# Tractive_System_Active_Light_rev4.net
KiCad netlist of a schematic drawn in EAGLE
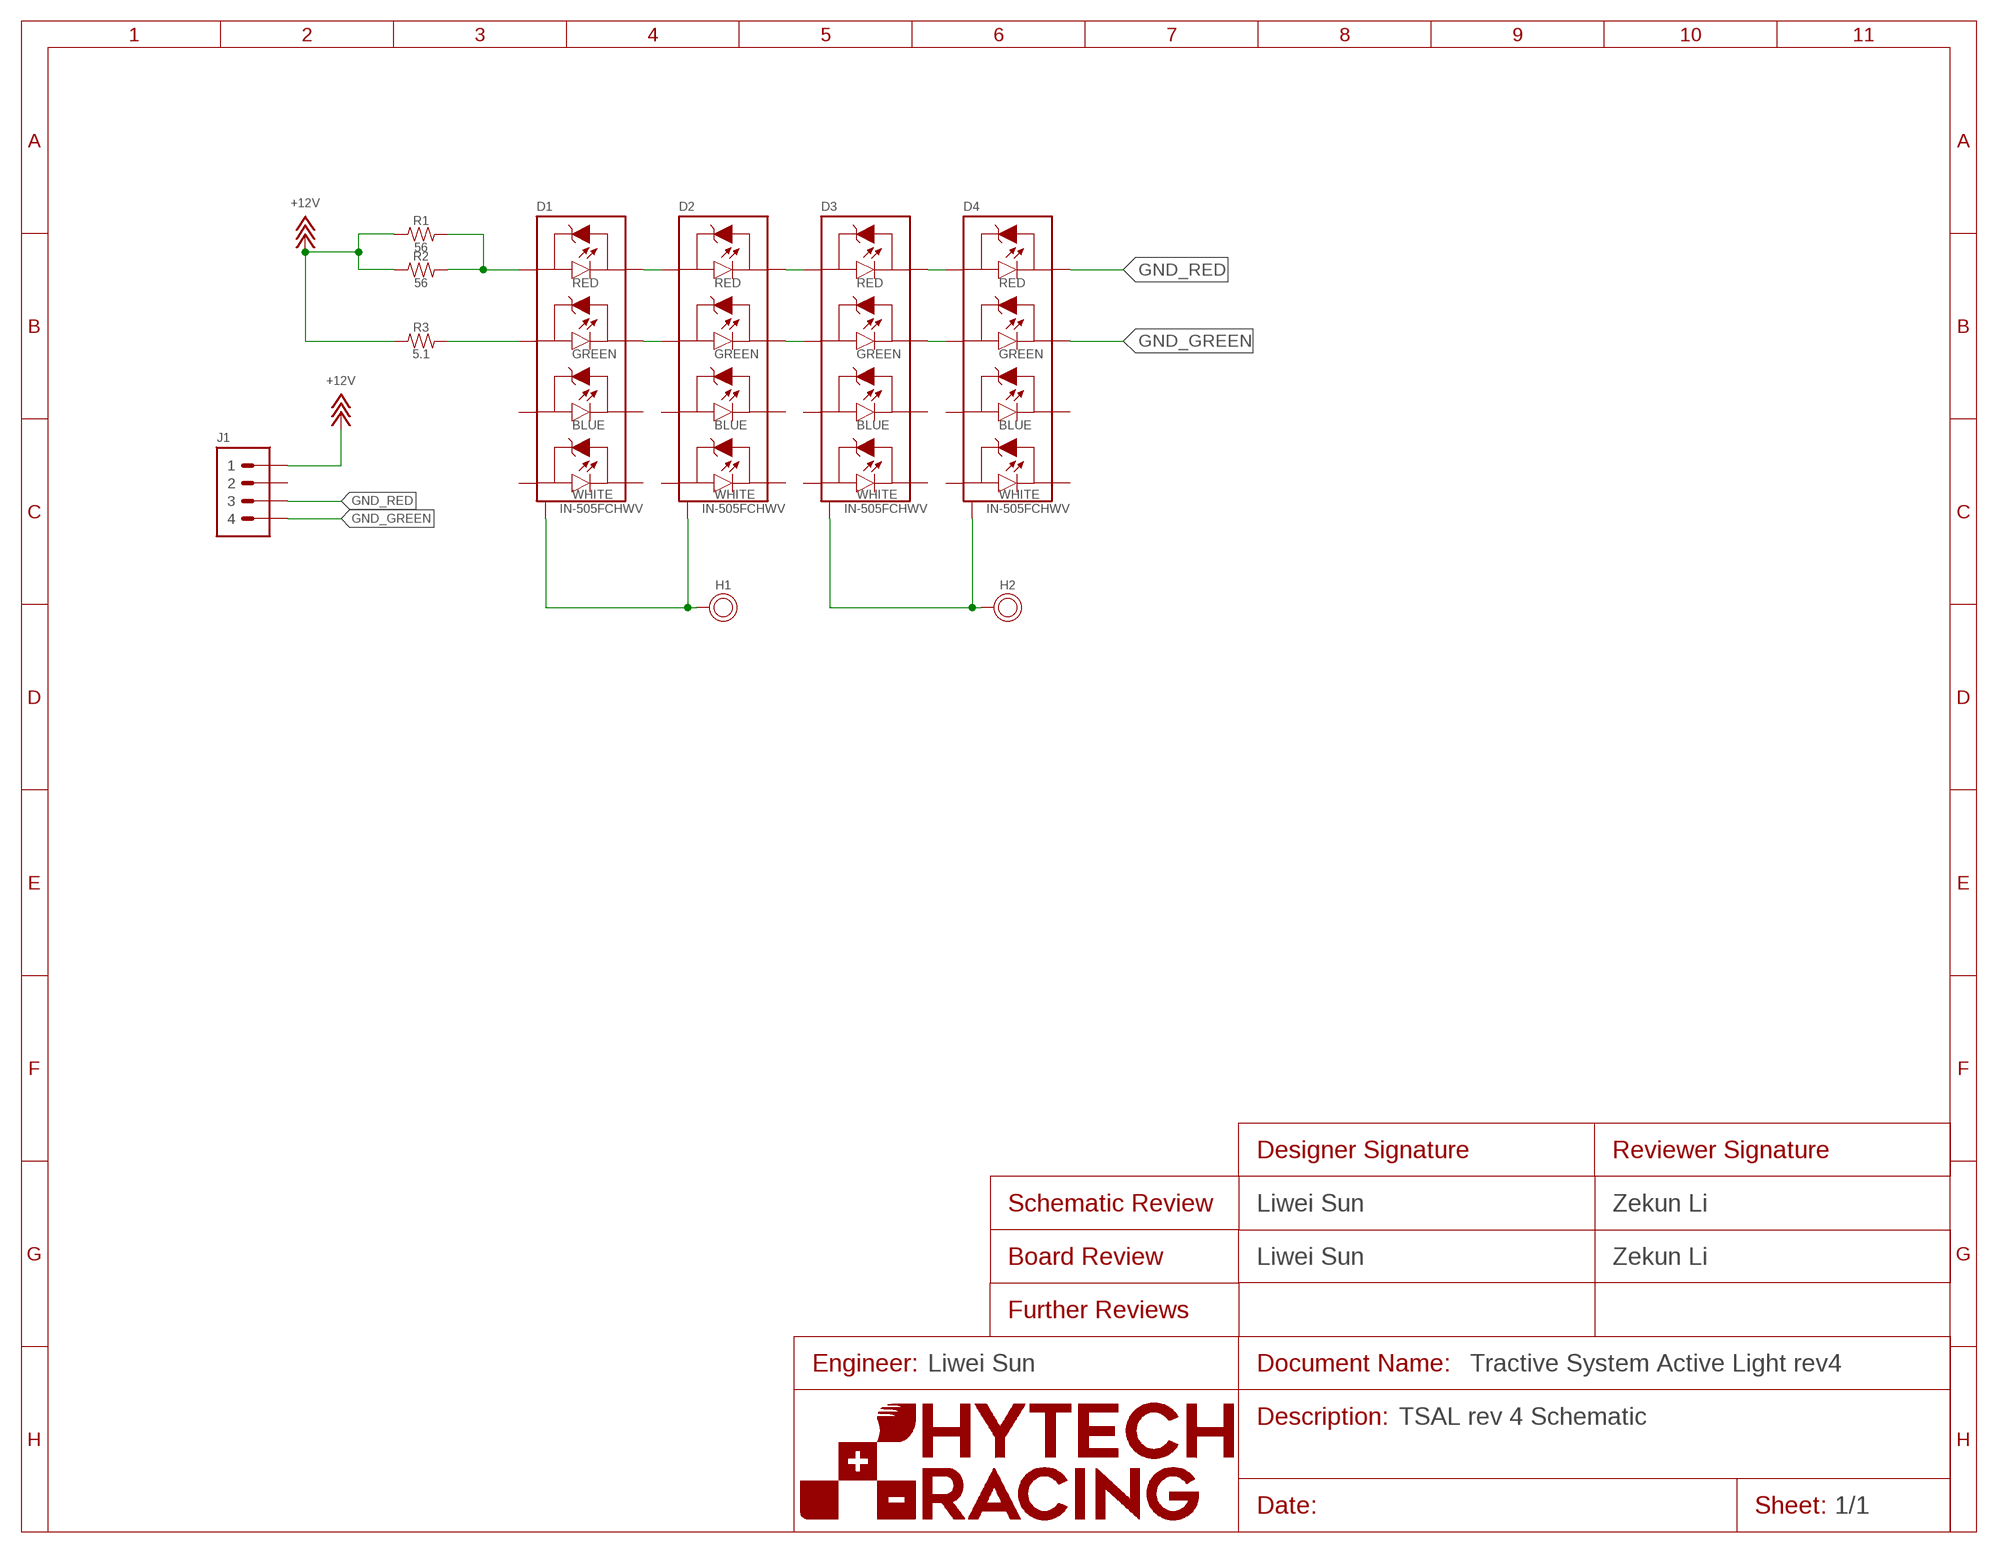
[diagram p0: schematic, sheet 1]

(export (version "E")
  (design (tool "Eeschema 10.0.6"))
  (components
    (comp (ref "D1")
      (value "LED_RGBW_IN-505FCHWV")
      (footprint "eagle-import:IN-505FCHWV")
      (fields (field (name "MPN") "IN-505FCHWV") (field (name "MANUFACTURER") "INOLUX"))
      (libsource (lib "eagle-import") (part "LED_RGBW_IN-505FCHWV"))
    )
    (comp (ref "D2")
      (value "LED_RGBW_IN-505FCHWV")
      (footprint "eagle-import:IN-505FCHWV")
      (fields (field (name "MPN") "IN-505FCHWV") (field (name "MANUFACTURER") "INOLUX"))
      (libsource (lib "eagle-import") (part "LED_RGBW_IN-505FCHWV"))
    )
    (comp (ref "D3")
      (value "LED_RGBW_IN-505FCHWV")
      (footprint "eagle-import:IN-505FCHWV")
      (fields (field (name "MPN") "IN-505FCHWV") (field (name "MANUFACTURER") "INOLUX"))
      (libsource (lib "eagle-import") (part "LED_RGBW_IN-505FCHWV"))
    )
    (comp (ref "D4")
      (value "LED_RGBW_IN-505FCHWV")
      (footprint "eagle-import:IN-505FCHWV")
      (fields (field (name "MPN") "IN-505FCHWV") (field (name "MANUFACTURER") "INOLUX"))
      (libsource (lib "eagle-import") (part "LED_RGBW_IN-505FCHWV"))
    )
    (comp (ref "H1")
      (value "MOUNTING_HEATSINK_M3")
      (footprint "eagle-import:MOUNTING_M3")
      (libsource (lib "eagle-import") (part "MOUNTING_HEATSINK_M3"))
    )
    (comp (ref "H2")
      (value "MOUNTING_HEATSINK_M3")
      (footprint "eagle-import:MOUNTING_M3")
      (libsource (lib "eagle-import") (part "MOUNTING_HEATSINK_M3"))
    )
    (comp (ref "J1")
      (value "CONNECTOR-4_μF_S_RA_")
      (footprint "eagle-import:MOLEX_MICROFIT_SMD_RIGHTANGLE_04_DUAL")
      (fields (field (name "MPN") "0430450411") (field (name "MANUFACTURER") "Molex"))
      (libsource (lib "eagle-import") (part "CONNECTOR-4_?_μF_S_RA"))
    )
    (comp (ref "R1")
      (value "RESISTOR_0805_56")
      (footprint "eagle-import:0805-RES")
      (fields
        (field (name "MANUFACTURER") "Panasonic Electronic Components")
        (field (name "MPN") "ERJ-P06D56R0V")
        (field (name "POWER") "0.5W")
        (field (name "RESISTANCE") "56")
      )
      (libsource (lib "eagle-import") (part "RESISTOR_?_080556"))
    )
    (comp (ref "R2")
      (value "RESISTOR_0805_56")
      (footprint "eagle-import:0805-RES")
      (fields
        (field (name "MANUFACTURER") "Panasonic Electronic Components")
        (field (name "MPN") "ERJ-P06D56R0V")
        (field (name "POWER") "0.5W")
        (field (name "RESISTANCE") "56")
      )
      (libsource (lib "eagle-import") (part "RESISTOR_?_080556"))
    )
    (comp (ref "R3")
      (value "RESISTOR_0603_5.1")
      (footprint "eagle-import:0603-RES")
      (fields
        (field (name "MANUFACTURER") "Panasonic Electronic Components")
        (field (name "MPN") "ERJ-P03J5R1V")
        (field (name "POWER") "0.25W")
        (field (name "RESISTANCE") "5.1")
      )
      (libsource (lib "eagle-import") (part "RESISTOR_?_06035.1"))
    )
  )
  (nets
    (net (code "1") (name "+12V") (class "Default")
      (node (ref "J1") (pin "1") (pinfunction "1_1") (pintype "passive"))
      (node (ref "R1") (pin "1") (pinfunction "1_1") (pintype "passive"))
      (node (ref "R2") (pin "1") (pinfunction "1_1") (pintype "passive"))
      (node (ref "R3") (pin "1") (pinfunction "1_1") (pintype "passive"))
    )
    (net (code "2") (name "GND_GREEN") (class "Default")
      (node (ref "D4") (pin "B-") (pinfunction "GREEN-_B-") (pintype "passive"))
      (node (ref "J1") (pin "4") (pinfunction "4_4") (pintype "passive"))
    )
    (net (code "3") (name "GND_RED") (class "Default")
      (node (ref "D4") (pin "A-") (pinfunction "RED-_A-") (pintype "passive"))
      (node (ref "J1") (pin "3") (pinfunction "3_3") (pintype "passive"))
    )
    (net (code "4") (name "Net-(D1-GREEN+)") (class "Default")
      (node (ref "D1") (pin "B+") (pinfunction "GREEN+_B+") (pintype "passive"))
      (node (ref "R3") (pin "2") (pinfunction "2_2") (pintype "passive"))
    )
    (net (code "5") (name "Net-(D1-GREEN-)") (class "Default")
      (node (ref "D1") (pin "B-") (pinfunction "GREEN-_B-") (pintype "passive"))
      (node (ref "D2") (pin "B+") (pinfunction "GREEN+_B+") (pintype "passive"))
    )
    (net (code "6") (name "Net-(D1-PadTHERMAL)") (class "Default")
      (node (ref "D1") (pin "THERMAL") (pinfunction "THERMAL_THERMAL") (pintype "passive"))
      (node (ref "D2") (pin "THERMAL") (pinfunction "THERMAL_THERMAL") (pintype "passive"))
      (node (ref "H1") (pin "P$1") (pinfunction "P$1_P$1") (pintype "passive"))
    )
    (net (code "7") (name "Net-(D1-RED+)") (class "Default")
      (node (ref "D1") (pin "A+") (pinfunction "RED+_A+") (pintype "passive"))
      (node (ref "R1") (pin "2") (pinfunction "2_2") (pintype "passive"))
      (node (ref "R2") (pin "2") (pinfunction "2_2") (pintype "passive"))
    )
    (net (code "8") (name "Net-(D1-RED-)") (class "Default")
      (node (ref "D1") (pin "A-") (pinfunction "RED-_A-") (pintype "passive"))
      (node (ref "D2") (pin "A+") (pinfunction "RED+_A+") (pintype "passive"))
    )
    (net (code "9") (name "Net-(D2-GREEN-)") (class "Default")
      (node (ref "D2") (pin "B-") (pinfunction "GREEN-_B-") (pintype "passive"))
      (node (ref "D3") (pin "B+") (pinfunction "GREEN+_B+") (pintype "passive"))
    )
    (net (code "10") (name "Net-(D2-RED-)") (class "Default")
      (node (ref "D2") (pin "A-") (pinfunction "RED-_A-") (pintype "passive"))
      (node (ref "D3") (pin "A+") (pinfunction "RED+_A+") (pintype "passive"))
    )
    (net (code "11") (name "Net-(D3-GREEN-)") (class "Default")
      (node (ref "D3") (pin "B-") (pinfunction "GREEN-_B-") (pintype "passive"))
      (node (ref "D4") (pin "B+") (pinfunction "GREEN+_B+") (pintype "passive"))
    )
    (net (code "12") (name "Net-(D3-PadTHERMAL)") (class "Default")
      (node (ref "D3") (pin "THERMAL") (pinfunction "THERMAL_THERMAL") (pintype "passive"))
      (node (ref "D4") (pin "THERMAL") (pinfunction "THERMAL_THERMAL") (pintype "passive"))
      (node (ref "H2") (pin "P$1") (pinfunction "P$1_P$1") (pintype "passive"))
    )
    (net (code "13") (name "Net-(D3-RED-)") (class "Default")
      (node (ref "D3") (pin "A-") (pinfunction "RED-_A-") (pintype "passive"))
      (node (ref "D4") (pin "A+") (pinfunction "RED+_A+") (pintype "passive"))
    )
    (net (code "14") (name "unconnected-(D1-BLUE+-PadC+)") (class "Default")
      (node (ref "D1") (pin "C+") (pinfunction "BLUE+_C+") (pintype "passive"))
    )
    (net (code "15") (name "unconnected-(D1-BLUE--PadC-)") (class "Default")
      (node (ref "D1") (pin "C-") (pinfunction "BLUE-_C-") (pintype "passive"))
    )
    (net (code "16") (name "unconnected-(D1-WHITE+-PadD+)") (class "Default")
      (node (ref "D1") (pin "D+") (pinfunction "WHITE+_D+") (pintype "passive"))
    )
    (net (code "17") (name "unconnected-(D1-WHITE--PadD-)") (class "Default")
      (node (ref "D1") (pin "D-") (pinfunction "WHITE-_D-") (pintype "passive"))
    )
    (net (code "18") (name "unconnected-(D2-BLUE+-PadC+)") (class "Default")
      (node (ref "D2") (pin "C+") (pinfunction "BLUE+_C+") (pintype "passive"))
    )
    (net (code "19") (name "unconnected-(D2-BLUE--PadC-)") (class "Default")
      (node (ref "D2") (pin "C-") (pinfunction "BLUE-_C-") (pintype "passive"))
    )
    (net (code "20") (name "unconnected-(D2-WHITE+-PadD+)") (class "Default")
      (node (ref "D2") (pin "D+") (pinfunction "WHITE+_D+") (pintype "passive"))
    )
    (net (code "21") (name "unconnected-(D2-WHITE--PadD-)") (class "Default")
      (node (ref "D2") (pin "D-") (pinfunction "WHITE-_D-") (pintype "passive"))
    )
    (net (code "22") (name "unconnected-(D3-BLUE+-PadC+)") (class "Default")
      (node (ref "D3") (pin "C+") (pinfunction "BLUE+_C+") (pintype "passive"))
    )
    (net (code "23") (name "unconnected-(D3-BLUE--PadC-)") (class "Default")
      (node (ref "D3") (pin "C-") (pinfunction "BLUE-_C-") (pintype "passive"))
    )
    (net (code "24") (name "unconnected-(D3-WHITE+-PadD+)") (class "Default")
      (node (ref "D3") (pin "D+") (pinfunction "WHITE+_D+") (pintype "passive"))
    )
    (net (code "25") (name "unconnected-(D3-WHITE--PadD-)") (class "Default")
      (node (ref "D3") (pin "D-") (pinfunction "WHITE-_D-") (pintype "passive"))
    )
    (net (code "26") (name "unconnected-(D4-BLUE+-PadC+)") (class "Default")
      (node (ref "D4") (pin "C+") (pinfunction "BLUE+_C+") (pintype "passive"))
    )
    (net (code "27") (name "unconnected-(D4-BLUE--PadC-)") (class "Default")
      (node (ref "D4") (pin "C-") (pinfunction "BLUE-_C-") (pintype "passive"))
    )
    (net (code "28") (name "unconnected-(D4-WHITE+-PadD+)") (class "Default")
      (node (ref "D4") (pin "D+") (pinfunction "WHITE+_D+") (pintype "passive"))
    )
    (net (code "29") (name "unconnected-(D4-WHITE--PadD-)") (class "Default")
      (node (ref "D4") (pin "D-") (pinfunction "WHITE-_D-") (pintype "passive"))
    )
    (net (code "30") (name "unconnected-(J1-Pad2)") (class "Default")
      (node (ref "J1") (pin "2") (pinfunction "2_2") (pintype "passive"))
    )
  )
)
